# single-gates-SMD.net
KiCad netlist of a schematic drawn in EAGLE
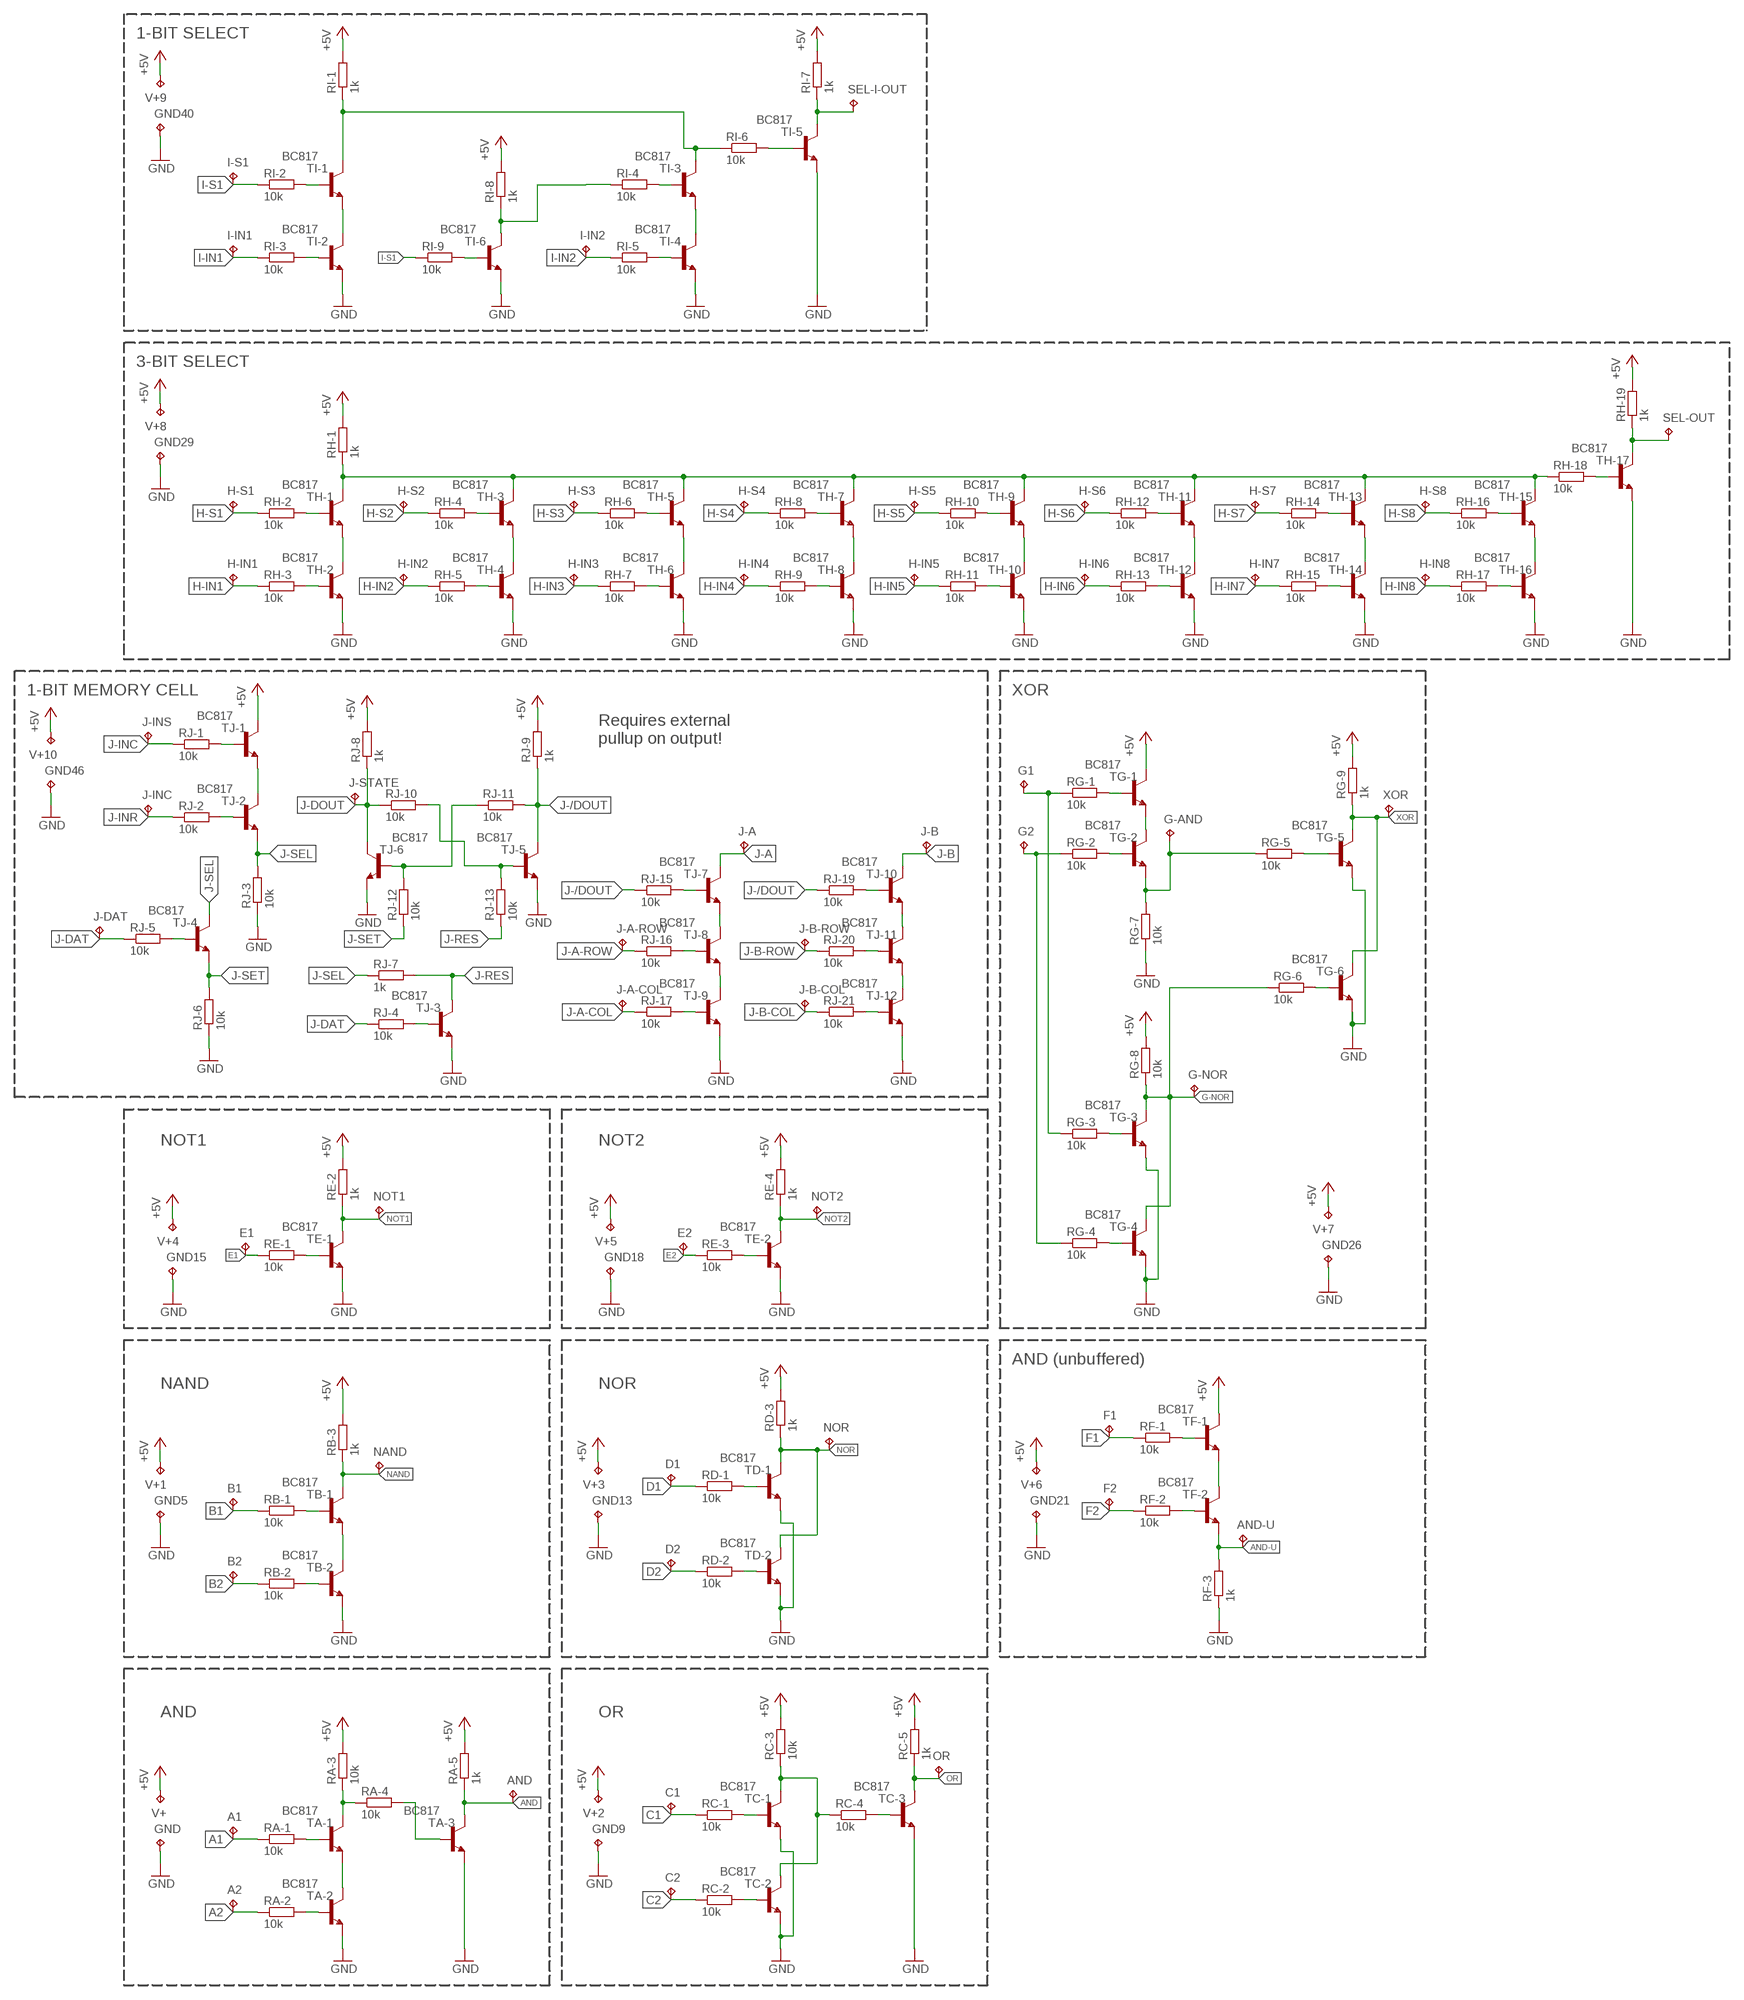
[diagram p0: schematic, sheet 1]

(export (version "E")
  (design (tool "Eeschema 10.0.6"))
  (components
    (comp (ref "A1")
      (value "TPTP07R")
      (footprint "eagle-import:TP07R")
      (libsource (lib "eagle-import") (part "TPTP07R"))
    )
    (comp (ref "A2")
      (value "TPTP07R")
      (footprint "eagle-import:TP07R")
      (libsource (lib "eagle-import") (part "TPTP07R"))
    )
    (comp (ref "AND")
      (value "TPTP07R")
      (footprint "eagle-import:TP07R")
      (libsource (lib "eagle-import") (part "TPTP07R"))
    )
    (comp (ref "AND-U")
      (value "TPTP07R")
      (footprint "eagle-import:TP07R")
      (libsource (lib "eagle-import") (part "TPTP07R"))
    )
    (comp (ref "B1")
      (value "TPTP07R")
      (footprint "eagle-import:TP07R")
      (libsource (lib "eagle-import") (part "TPTP07R"))
    )
    (comp (ref "B2")
      (value "TPTP07R")
      (footprint "eagle-import:TP07R")
      (libsource (lib "eagle-import") (part "TPTP07R"))
    )
    (comp (ref "C1")
      (value "TPTP07R")
      (footprint "eagle-import:TP07R")
      (libsource (lib "eagle-import") (part "TPTP07R"))
    )
    (comp (ref "C2")
      (value "TPTP07R")
      (footprint "eagle-import:TP07R")
      (libsource (lib "eagle-import") (part "TPTP07R"))
    )
    (comp (ref "D1")
      (value "TPTP07R")
      (footprint "eagle-import:TP07R")
      (libsource (lib "eagle-import") (part "TPTP07R"))
    )
    (comp (ref "D2")
      (value "TPTP07R")
      (footprint "eagle-import:TP07R")
      (libsource (lib "eagle-import") (part "TPTP07R"))
    )
    (comp (ref "E1")
      (value "TPTP07R")
      (footprint "eagle-import:TP07R")
      (libsource (lib "eagle-import") (part "TPTP07R"))
    )
    (comp (ref "E2")
      (value "TPTP07R")
      (footprint "eagle-import:TP07R")
      (libsource (lib "eagle-import") (part "TPTP07R"))
    )
    (comp (ref "F1")
      (value "TPTP07R")
      (footprint "eagle-import:TP07R")
      (libsource (lib "eagle-import") (part "TPTP07R"))
    )
    (comp (ref "F2")
      (value "TPTP07R")
      (footprint "eagle-import:TP07R")
      (libsource (lib "eagle-import") (part "TPTP07R"))
    )
    (comp (ref "G-AND")
      (value "TPTP07R")
      (footprint "eagle-import:TP07R")
      (libsource (lib "eagle-import") (part "TPTP07R"))
    )
    (comp (ref "G-NOR")
      (value "TPTP07R")
      (footprint "eagle-import:TP07R")
      (libsource (lib "eagle-import") (part "TPTP07R"))
    )
    (comp (ref "G1")
      (value "TPTP07R")
      (footprint "eagle-import:TP07R")
      (libsource (lib "eagle-import") (part "TPTP07R"))
    )
    (comp (ref "G2")
      (value "TPTP07R")
      (footprint "eagle-import:TP07R")
      (libsource (lib "eagle-import") (part "TPTP07R"))
    )
    (comp (ref "GND")
      (value "TPTP07R")
      (footprint "eagle-import:TP07R")
      (libsource (lib "eagle-import") (part "TPTP07R"))
    )
    (comp (ref "GND5")
      (value "TPTP07R")
      (footprint "eagle-import:TP07R")
      (libsource (lib "eagle-import") (part "TPTP07R"))
    )
    (comp (ref "GND9")
      (value "TPTP07R")
      (footprint "eagle-import:TP07R")
      (libsource (lib "eagle-import") (part "TPTP07R"))
    )
    (comp (ref "GND13")
      (value "TPTP07R")
      (footprint "eagle-import:TP07R")
      (libsource (lib "eagle-import") (part "TPTP07R"))
    )
    (comp (ref "GND15")
      (value "TPTP07R")
      (footprint "eagle-import:TP07R")
      (libsource (lib "eagle-import") (part "TPTP07R"))
    )
    (comp (ref "GND18")
      (value "TPTP07R")
      (footprint "eagle-import:TP07R")
      (libsource (lib "eagle-import") (part "TPTP07R"))
    )
    (comp (ref "GND21")
      (value "TPTP07R")
      (footprint "eagle-import:TP07R")
      (libsource (lib "eagle-import") (part "TPTP07R"))
    )
    (comp (ref "GND26")
      (value "TPTP07R")
      (footprint "eagle-import:TP07R")
      (libsource (lib "eagle-import") (part "TPTP07R"))
    )
    (comp (ref "GND29")
      (value "TPTP07R")
      (footprint "eagle-import:TP07R")
      (libsource (lib "eagle-import") (part "TPTP07R"))
    )
    (comp (ref "GND40")
      (value "TPTP07R")
      (footprint "eagle-import:TP07R")
      (libsource (lib "eagle-import") (part "TPTP07R"))
    )
    (comp (ref "GND46")
      (value "TPTP07R")
      (footprint "eagle-import:TP07R")
      (libsource (lib "eagle-import") (part "TPTP07R"))
    )
    (comp (ref "H-IN1")
      (value "TPTP07R")
      (footprint "eagle-import:TP07R")
      (libsource (lib "eagle-import") (part "TPTP07R"))
    )
    (comp (ref "H-IN2")
      (value "TPTP07R")
      (footprint "eagle-import:TP07R")
      (libsource (lib "eagle-import") (part "TPTP07R"))
    )
    (comp (ref "H-IN3")
      (value "TPTP07R")
      (footprint "eagle-import:TP07R")
      (libsource (lib "eagle-import") (part "TPTP07R"))
    )
    (comp (ref "H-IN4")
      (value "TPTP07R")
      (footprint "eagle-import:TP07R")
      (libsource (lib "eagle-import") (part "TPTP07R"))
    )
    (comp (ref "H-IN5")
      (value "TPTP07R")
      (footprint "eagle-import:TP07R")
      (libsource (lib "eagle-import") (part "TPTP07R"))
    )
    (comp (ref "H-IN6")
      (value "TPTP07R")
      (footprint "eagle-import:TP07R")
      (libsource (lib "eagle-import") (part "TPTP07R"))
    )
    (comp (ref "H-IN7")
      (value "TPTP07R")
      (footprint "eagle-import:TP07R")
      (libsource (lib "eagle-import") (part "TPTP07R"))
    )
    (comp (ref "H-IN8")
      (value "TPTP07R")
      (footprint "eagle-import:TP07R")
      (libsource (lib "eagle-import") (part "TPTP07R"))
    )
    (comp (ref "H-S1")
      (value "TPTP07R")
      (footprint "eagle-import:TP07R")
      (libsource (lib "eagle-import") (part "TPTP07R"))
    )
    (comp (ref "H-S2")
      (value "TPTP07R")
      (footprint "eagle-import:TP07R")
      (libsource (lib "eagle-import") (part "TPTP07R"))
    )
    (comp (ref "H-S3")
      (value "TPTP07R")
      (footprint "eagle-import:TP07R")
      (libsource (lib "eagle-import") (part "TPTP07R"))
    )
    (comp (ref "H-S4")
      (value "TPTP07R")
      (footprint "eagle-import:TP07R")
      (libsource (lib "eagle-import") (part "TPTP07R"))
    )
    (comp (ref "H-S5")
      (value "TPTP07R")
      (footprint "eagle-import:TP07R")
      (libsource (lib "eagle-import") (part "TPTP07R"))
    )
    (comp (ref "H-S6")
      (value "TPTP07R")
      (footprint "eagle-import:TP07R")
      (libsource (lib "eagle-import") (part "TPTP07R"))
    )
    (comp (ref "H-S7")
      (value "TPTP07R")
      (footprint "eagle-import:TP07R")
      (libsource (lib "eagle-import") (part "TPTP07R"))
    )
    (comp (ref "H-S8")
      (value "TPTP07R")
      (footprint "eagle-import:TP07R")
      (libsource (lib "eagle-import") (part "TPTP07R"))
    )
    (comp (ref "I-IN1")
      (value "TPTP07R")
      (footprint "eagle-import:TP07R")
      (libsource (lib "eagle-import") (part "TPTP07R"))
    )
    (comp (ref "I-IN2")
      (value "TPTP07R")
      (footprint "eagle-import:TP07R")
      (libsource (lib "eagle-import") (part "TPTP07R"))
    )
    (comp (ref "I-S1")
      (value "TPTP07R")
      (footprint "eagle-import:TP07R")
      (libsource (lib "eagle-import") (part "TPTP07R"))
    )
    (comp (ref "J-A")
      (value "TPTP07R")
      (footprint "eagle-import:TP07R")
      (libsource (lib "eagle-import") (part "TPTP07R"))
    )
    (comp (ref "J-A-COL")
      (value "TPTP07R")
      (footprint "eagle-import:TP07R")
      (libsource (lib "eagle-import") (part "TPTP07R"))
    )
    (comp (ref "J-A-ROW")
      (value "TPTP07R")
      (footprint "eagle-import:TP07R")
      (libsource (lib "eagle-import") (part "TPTP07R"))
    )
    (comp (ref "J-B")
      (value "TPTP07R")
      (footprint "eagle-import:TP07R")
      (libsource (lib "eagle-import") (part "TPTP07R"))
    )
    (comp (ref "J-B-COL")
      (value "TPTP07R")
      (footprint "eagle-import:TP07R")
      (libsource (lib "eagle-import") (part "TPTP07R"))
    )
    (comp (ref "J-B-ROW")
      (value "TPTP07R")
      (footprint "eagle-import:TP07R")
      (libsource (lib "eagle-import") (part "TPTP07R"))
    )
    (comp (ref "J-DAT")
      (value "TPTP07R")
      (footprint "eagle-import:TP07R")
      (libsource (lib "eagle-import") (part "TPTP07R"))
    )
    (comp (ref "J-INC")
      (value "TPTP07R")
      (footprint "eagle-import:TP07R")
      (libsource (lib "eagle-import") (part "TPTP07R"))
    )
    (comp (ref "J-INS")
      (value "TPTP07R")
      (footprint "eagle-import:TP07R")
      (libsource (lib "eagle-import") (part "TPTP07R"))
    )
    (comp (ref "J-STATE")
      (value "TPTP07R")
      (footprint "eagle-import:TP07R")
      (libsource (lib "eagle-import") (part "TPTP07R"))
    )
    (comp (ref "NAND")
      (value "TPTP07R")
      (footprint "eagle-import:TP07R")
      (libsource (lib "eagle-import") (part "TPTP07R"))
    )
    (comp (ref "NOR")
      (value "TPTP07R")
      (footprint "eagle-import:TP07R")
      (libsource (lib "eagle-import") (part "TPTP07R"))
    )
    (comp (ref "NOT1")
      (value "TPTP07R")
      (footprint "eagle-import:TP07R")
      (libsource (lib "eagle-import") (part "TPTP07R"))
    )
    (comp (ref "NOT2")
      (value "TPTP07R")
      (footprint "eagle-import:TP07R")
      (libsource (lib "eagle-import") (part "TPTP07R"))
    )
    (comp (ref "OR")
      (value "TPTP07R")
      (footprint "eagle-import:TP07R")
      (libsource (lib "eagle-import") (part "TPTP07R"))
    )
    (comp (ref "RA-1")
      (value "10k")
      (footprint "eagle-import:R0603")
      (libsource (lib "eagle-import") (part "R-EU_R0603"))
    )
    (comp (ref "RA-2")
      (value "10k")
      (footprint "eagle-import:R0603")
      (libsource (lib "eagle-import") (part "R-EU_R0603"))
    )
    (comp (ref "RA-3")
      (value "10k")
      (footprint "eagle-import:R0603")
      (libsource (lib "eagle-import") (part "R-EU_R0603"))
    )
    (comp (ref "RA-4")
      (value "10k")
      (footprint "eagle-import:R0603")
      (libsource (lib "eagle-import") (part "R-EU_R0603"))
    )
    (comp (ref "RA-5")
      (value "1k")
      (footprint "eagle-import:R0603")
      (libsource (lib "eagle-import") (part "R-EU_R0603"))
    )
    (comp (ref "RB-1")
      (value "10k")
      (footprint "eagle-import:R0603")
      (libsource (lib "eagle-import") (part "R-EU_R0603"))
    )
    (comp (ref "RB-2")
      (value "10k")
      (footprint "eagle-import:R0603")
      (libsource (lib "eagle-import") (part "R-EU_R0603"))
    )
    (comp (ref "RB-3")
      (value "1k")
      (footprint "eagle-import:R0603")
      (libsource (lib "eagle-import") (part "R-EU_R0603"))
    )
    (comp (ref "RC-1")
      (value "10k")
      (footprint "eagle-import:R0603")
      (libsource (lib "eagle-import") (part "R-EU_R0603"))
    )
    (comp (ref "RC-2")
      (value "10k")
      (footprint "eagle-import:R0603")
      (libsource (lib "eagle-import") (part "R-EU_R0603"))
    )
    (comp (ref "RC-3")
      (value "10k")
      (footprint "eagle-import:R0603")
      (libsource (lib "eagle-import") (part "R-EU_R0603"))
    )
    (comp (ref "RC-4")
      (value "10k")
      (footprint "eagle-import:R0603")
      (libsource (lib "eagle-import") (part "R-EU_R0603"))
    )
    (comp (ref "RC-5")
      (value "1k")
      (footprint "eagle-import:R0603")
      (libsource (lib "eagle-import") (part "R-EU_R0603"))
    )
    (comp (ref "RD-1")
      (value "10k")
      (footprint "eagle-import:R0603")
      (libsource (lib "eagle-import") (part "R-EU_R0603"))
    )
    (comp (ref "RD-2")
      (value "10k")
      (footprint "eagle-import:R0603")
      (libsource (lib "eagle-import") (part "R-EU_R0603"))
    )
    (comp (ref "RD-3")
      (value "1k")
      (footprint "eagle-import:R0603")
      (libsource (lib "eagle-import") (part "R-EU_R0603"))
    )
    (comp (ref "RE-1")
      (value "10k")
      (footprint "eagle-import:R0603")
      (libsource (lib "eagle-import") (part "R-EU_R0603"))
    )
    (comp (ref "RE-2")
      (value "1k")
      (footprint "eagle-import:R0603")
      (libsource (lib "eagle-import") (part "R-EU_R0603"))
    )
    (comp (ref "RE-3")
      (value "10k")
      (footprint "eagle-import:R0603")
      (libsource (lib "eagle-import") (part "R-EU_R0603"))
    )
    (comp (ref "RE-4")
      (value "1k")
      (footprint "eagle-import:R0603")
      (libsource (lib "eagle-import") (part "R-EU_R0603"))
    )
    (comp (ref "RF-1")
      (value "10k")
      (footprint "eagle-import:R0603")
      (libsource (lib "eagle-import") (part "R-EU_R0603"))
    )
    (comp (ref "RF-2")
      (value "10k")
      (footprint "eagle-import:R0603")
      (libsource (lib "eagle-import") (part "R-EU_R0603"))
    )
    (comp (ref "RF-3")
      (value "1k")
      (footprint "eagle-import:R0603")
      (libsource (lib "eagle-import") (part "R-EU_R0603"))
    )
    (comp (ref "RG-1")
      (value "10k")
      (footprint "eagle-import:R0603")
      (libsource (lib "eagle-import") (part "R-EU_R0603"))
    )
    (comp (ref "RG-2")
      (value "10k")
      (footprint "eagle-import:R0603")
      (libsource (lib "eagle-import") (part "R-EU_R0603"))
    )
    (comp (ref "RG-3")
      (value "10k")
      (footprint "eagle-import:R0603")
      (libsource (lib "eagle-import") (part "R-EU_R0603"))
    )
    (comp (ref "RG-4")
      (value "10k")
      (footprint "eagle-import:R0603")
      (libsource (lib "eagle-import") (part "R-EU_R0603"))
    )
    (comp (ref "RG-5")
      (value "10k")
      (footprint "eagle-import:R0603")
      (libsource (lib "eagle-import") (part "R-EU_R0603"))
    )
    (comp (ref "RG-6")
      (value "10k")
      (footprint "eagle-import:R0603")
      (libsource (lib "eagle-import") (part "R-EU_R0603"))
    )
    (comp (ref "RG-7")
      (value "10k")
      (footprint "eagle-import:R0603")
      (libsource (lib "eagle-import") (part "R-EU_R0603"))
    )
    (comp (ref "RG-8")
      (value "10k")
      (footprint "eagle-import:R0603")
      (libsource (lib "eagle-import") (part "R-EU_R0603"))
    )
    (comp (ref "RG-9")
      (value "1k")
      (footprint "eagle-import:R0603")
      (libsource (lib "eagle-import") (part "R-EU_R0603"))
    )
    (comp (ref "RH-1")
      (value "1k")
      (footprint "eagle-import:R0603")
      (libsource (lib "eagle-import") (part "R-EU_R0603"))
    )
    (comp (ref "RH-2")
      (value "10k")
      (footprint "eagle-import:R0603")
      (libsource (lib "eagle-import") (part "R-EU_R0603"))
    )
    (comp (ref "RH-3")
      (value "10k")
      (footprint "eagle-import:R0603")
      (libsource (lib "eagle-import") (part "R-EU_R0603"))
    )
    (comp (ref "RH-4")
      (value "10k")
      (footprint "eagle-import:R0603")
      (libsource (lib "eagle-import") (part "R-EU_R0603"))
    )
    (comp (ref "RH-5")
      (value "10k")
      (footprint "eagle-import:R0603")
      (libsource (lib "eagle-import") (part "R-EU_R0603"))
    )
    (comp (ref "RH-6")
      (value "10k")
      (footprint "eagle-import:R0603")
      (libsource (lib "eagle-import") (part "R-EU_R0603"))
    )
    (comp (ref "RH-7")
      (value "10k")
      (footprint "eagle-import:R0603")
      (libsource (lib "eagle-import") (part "R-EU_R0603"))
    )
    (comp (ref "RH-8")
      (value "10k")
      (footprint "eagle-import:R0603")
      (libsource (lib "eagle-import") (part "R-EU_R0603"))
    )
    (comp (ref "RH-9")
      (value "10k")
      (footprint "eagle-import:R0603")
      (libsource (lib "eagle-import") (part "R-EU_R0603"))
    )
    (comp (ref "RH-10")
      (value "10k")
      (footprint "eagle-import:R0603")
      (libsource (lib "eagle-import") (part "R-EU_R0603"))
    )
    (comp (ref "RH-11")
      (value "10k")
      (footprint "eagle-import:R0603")
      (libsource (lib "eagle-import") (part "R-EU_R0603"))
    )
    (comp (ref "RH-12")
      (value "10k")
      (footprint "eagle-import:R0603")
      (libsource (lib "eagle-import") (part "R-EU_R0603"))
    )
    (comp (ref "RH-13")
      (value "10k")
      (footprint "eagle-import:R0603")
      (libsource (lib "eagle-import") (part "R-EU_R0603"))
    )
    (comp (ref "RH-14")
      (value "10k")
      (footprint "eagle-import:R0603")
      (libsource (lib "eagle-import") (part "R-EU_R0603"))
    )
    (comp (ref "RH-15")
      (value "10k")
      (footprint "eagle-import:R0603")
      (libsource (lib "eagle-import") (part "R-EU_R0603"))
    )
    (comp (ref "RH-16")
      (value "10k")
      (footprint "eagle-import:R0603")
      (libsource (lib "eagle-import") (part "R-EU_R0603"))
    )
    (comp (ref "RH-17")
      (value "10k")
      (footprint "eagle-import:R0603")
      (libsource (lib "eagle-import") (part "R-EU_R0603"))
    )
    (comp (ref "RH-18")
      (value "10k")
      (footprint "eagle-import:R0603")
      (libsource (lib "eagle-import") (part "R-EU_R0603"))
    )
    (comp (ref "RH-19")
      (value "1k")
      (footprint "eagle-import:R0603")
      (libsource (lib "eagle-import") (part "R-EU_R0603"))
    )
    (comp (ref "RI-1")
      (value "1k")
      (footprint "eagle-import:R0603")
      (libsource (lib "eagle-import") (part "R-EU_R0603"))
    )
    (comp (ref "RI-2")
      (value "10k")
      (footprint "eagle-import:R0603")
      (libsource (lib "eagle-import") (part "R-EU_R0603"))
    )
    (comp (ref "RI-3")
      (value "10k")
      (footprint "eagle-import:R0603")
      (libsource (lib "eagle-import") (part "R-EU_R0603"))
    )
    (comp (ref "RI-4")
      (value "10k")
      (footprint "eagle-import:R0603")
      (libsource (lib "eagle-import") (part "R-EU_R0603"))
    )
    (comp (ref "RI-5")
      (value "10k")
      (footprint "eagle-import:R0603")
      (libsource (lib "eagle-import") (part "R-EU_R0603"))
    )
    (comp (ref "RI-6")
      (value "10k")
      (footprint "eagle-import:R0603")
      (libsource (lib "eagle-import") (part "R-EU_R0603"))
    )
    (comp (ref "RI-7")
      (value "1k")
      (footprint "eagle-import:R0603")
      (libsource (lib "eagle-import") (part "R-EU_R0603"))
    )
    (comp (ref "RI-8")
      (value "1k")
      (footprint "eagle-import:R0603")
      (libsource (lib "eagle-import") (part "R-EU_R0603"))
    )
    (comp (ref "RI-9")
      (value "10k")
      (footprint "eagle-import:R0603")
      (libsource (lib "eagle-import") (part "R-EU_R0603"))
    )
    (comp (ref "RJ-1")
      (value "10k")
      (footprint "eagle-import:R0603")
      (libsource (lib "eagle-import") (part "R-EU_R0603"))
    )
    (comp (ref "RJ-2")
      (value "10k")
      (footprint "eagle-import:R0603")
      (libsource (lib "eagle-import") (part "R-EU_R0603"))
    )
    (comp (ref "RJ-3")
      (value "10k")
      (footprint "eagle-import:R0603")
      (libsource (lib "eagle-import") (part "R-EU_R0603"))
    )
    (comp (ref "RJ-4")
      (value "10k")
      (footprint "eagle-import:R0603")
      (libsource (lib "eagle-import") (part "R-EU_R0603"))
    )
    (comp (ref "RJ-5")
      (value "10k")
      (footprint "eagle-import:R0603")
      (libsource (lib "eagle-import") (part "R-EU_R0603"))
    )
    (comp (ref "RJ-6")
      (value "10k")
      (footprint "eagle-import:R0603")
      (libsource (lib "eagle-import") (part "R-EU_R0603"))
    )
    (comp (ref "RJ-7")
      (value "1k")
      (footprint "eagle-import:R0603")
      (libsource (lib "eagle-import") (part "R-EU_R0603"))
    )
    (comp (ref "RJ-8")
      (value "1k")
      (footprint "eagle-import:R0603")
      (libsource (lib "eagle-import") (part "R-EU_R0603"))
    )
    (comp (ref "RJ-9")
      (value "1k")
      (footprint "eagle-import:R0603")
      (libsource (lib "eagle-import") (part "R-EU_R0603"))
    )
    (comp (ref "RJ-10")
      (value "10k")
      (footprint "eagle-import:R0603")
      (libsource (lib "eagle-import") (part "R-EU_R0603"))
    )
    (comp (ref "RJ-11")
      (value "10k")
      (footprint "eagle-import:R0603")
      (libsource (lib "eagle-import") (part "R-EU_R0603"))
    )
    (comp (ref "RJ-12")
      (value "10k")
      (footprint "eagle-import:R0603")
      (libsource (lib "eagle-import") (part "R-EU_R0603"))
    )
    (comp (ref "RJ-13")
      (value "10k")
      (footprint "eagle-import:R0603")
      (libsource (lib "eagle-import") (part "R-EU_R0603"))
    )
    (comp (ref "RJ-15")
      (value "10k")
      (footprint "eagle-import:R0603")
      (libsource (lib "eagle-import") (part "R-EU_R0603"))
    )
    (comp (ref "RJ-16")
      (value "10k")
      (footprint "eagle-import:R0603")
      (libsource (lib "eagle-import") (part "R-EU_R0603"))
    )
    (comp (ref "RJ-17")
      (value "10k")
      (footprint "eagle-import:R0603")
      (libsource (lib "eagle-import") (part "R-EU_R0603"))
    )
    (comp (ref "RJ-19")
      (value "10k")
      (footprint "eagle-import:R0603")
      (libsource (lib "eagle-import") (part "R-EU_R0603"))
    )
    (comp (ref "RJ-20")
      (value "10k")
      (footprint "eagle-import:R0603")
      (libsource (lib "eagle-import") (part "R-EU_R0603"))
    )
    (comp (ref "RJ-21")
      (value "10k")
      (footprint "eagle-import:R0603")
      (libsource (lib "eagle-import") (part "R-EU_R0603"))
    )
    (comp (ref "SEL-I-OUT")
      (value "TPTP07R")
      (footprint "eagle-import:TP07R")
      (libsource (lib "eagle-import") (part "TPTP07R"))
    )
    (comp (ref "SEL-OUT")
      (value "TPTP07R")
      (footprint "eagle-import:TP07R")
      (libsource (lib "eagle-import") (part "TPTP07R"))
    )
    (comp (ref "TA-1")
      (value "BC817")
      (footprint "eagle-import:SOT23-BEC")
      (libsource (lib "eagle-import") (part "-NPN-SOT23-BECBC817-40"))
    )
    (comp (ref "TA-2")
      (value "BC817")
      (footprint "eagle-import:SOT23-BEC")
      (libsource (lib "eagle-import") (part "-NPN-SOT23-BECBC817-40"))
    )
    (comp (ref "TA-3")
      (value "BC817")
      (footprint "eagle-import:SOT23-BEC")
      (libsource (lib "eagle-import") (part "-NPN-SOT23-BECBC817-40"))
    )
    (comp (ref "TB-1")
      (value "BC817")
      (footprint "eagle-import:SOT23-BEC")
      (libsource (lib "eagle-import") (part "-NPN-SOT23-BECBC817-40"))
    )
    (comp (ref "TB-2")
      (value "BC817")
      (footprint "eagle-import:SOT23-BEC")
      (libsource (lib "eagle-import") (part "-NPN-SOT23-BECBC817-40"))
    )
    (comp (ref "TC-1")
      (value "BC817")
      (footprint "eagle-import:SOT23-BEC")
      (libsource (lib "eagle-import") (part "-NPN-SOT23-BECBC817-40"))
    )
    (comp (ref "TC-2")
      (value "BC817")
      (footprint "eagle-import:SOT23-BEC")
      (libsource (lib "eagle-import") (part "-NPN-SOT23-BECBC817-40"))
    )
    (comp (ref "TC-3")
      (value "BC817")
      (footprint "eagle-import:SOT23-BEC")
      (libsource (lib "eagle-import") (part "-NPN-SOT23-BECBC817-40"))
    )
    (comp (ref "TD-1")
      (value "BC817")
      (footprint "eagle-import:SOT23-BEC")
      (libsource (lib "eagle-import") (part "-NPN-SOT23-BECBC817-40"))
    )
    (comp (ref "TD-2")
      (value "BC817")
      (footprint "eagle-import:SOT23-BEC")
      (libsource (lib "eagle-import") (part "-NPN-SOT23-BECBC817-40"))
    )
    (comp (ref "TE-1")
      (value "BC817")
      (footprint "eagle-import:SOT23-BEC")
      (libsource (lib "eagle-import") (part "-NPN-SOT23-BECBC817-40"))
    )
    (comp (ref "TE-2")
      (value "BC817")
      (footprint "eagle-import:SOT23-BEC")
      (libsource (lib "eagle-import") (part "-NPN-SOT23-BECBC817-40"))
    )
    (comp (ref "TF-1")
      (value "BC817")
      (footprint "eagle-import:SOT23-BEC")
      (libsource (lib "eagle-import") (part "-NPN-SOT23-BECBC817-40"))
    )
    (comp (ref "TF-2")
      (value "BC817")
      (footprint "eagle-import:SOT23-BEC")
      (libsource (lib "eagle-import") (part "-NPN-SOT23-BECBC817-40"))
    )
    (comp (ref "TG-1")
      (value "BC817")
      (footprint "eagle-import:SOT23-BEC")
      (libsource (lib "eagle-import") (part "-NPN-SOT23-BECBC817-40"))
    )
    (comp (ref "TG-2")
      (value "BC817")
      (footprint "eagle-import:SOT23-BEC")
      (libsource (lib "eagle-import") (part "-NPN-SOT23-BECBC817-40"))
    )
    (comp (ref "TG-3")
      (value "BC817")
      (footprint "eagle-import:SOT23-BEC")
      (libsource (lib "eagle-import") (part "-NPN-SOT23-BECBC817-40"))
    )
    (comp (ref "TG-4")
      (value "BC817")
      (footprint "eagle-import:SOT23-BEC")
      (libsource (lib "eagle-import") (part "-NPN-SOT23-BECBC817-40"))
    )
    (comp (ref "TG-5")
      (value "BC817")
      (footprint "eagle-import:SOT23-BEC")
      (libsource (lib "eagle-import") (part "-NPN-SOT23-BECBC817-40"))
    )
    (comp (ref "TG-6")
      (value "BC817")
      (footprint "eagle-import:SOT23-BEC")
      (libsource (lib "eagle-import") (part "-NPN-SOT23-BECBC817-40"))
    )
    (comp (ref "TH-1")
      (value "BC817")
      (footprint "eagle-import:SOT23-BEC")
      (libsource (lib "eagle-import") (part "-NPN-SOT23-BECBC817-40"))
    )
    (comp (ref "TH-2")
      (value "BC817")
      (footprint "eagle-import:SOT23-BEC")
      (libsource (lib "eagle-import") (part "-NPN-SOT23-BECBC817-40"))
    )
    (comp (ref "TH-3")
      (value "BC817")
      (footprint "eagle-import:SOT23-BEC")
      (libsource (lib "eagle-import") (part "-NPN-SOT23-BECBC817-40"))
    )
    (comp (ref "TH-4")
      (value "BC817")
      (footprint "eagle-import:SOT23-BEC")
      (libsource (lib "eagle-import") (part "-NPN-SOT23-BECBC817-40"))
    )
    (comp (ref "TH-5")
      (value "BC817")
      (footprint "eagle-import:SOT23-BEC")
      (libsource (lib "eagle-import") (part "-NPN-SOT23-BECBC817-40"))
    )
    (comp (ref "TH-6")
      (value "BC817")
      (footprint "eagle-import:SOT23-BEC")
      (libsource (lib "eagle-import") (part "-NPN-SOT23-BECBC817-40"))
    )
    (comp (ref "TH-7")
      (value "BC817")
      (footprint "eagle-import:SOT23-BEC")
      (libsource (lib "eagle-import") (part "-NPN-SOT23-BECBC817-40"))
    )
    (comp (ref "TH-8")
      (value "BC817")
      (footprint "eagle-import:SOT23-BEC")
      (libsource (lib "eagle-import") (part "-NPN-SOT23-BECBC817-40"))
    )
    (comp (ref "TH-9")
      (value "BC817")
      (footprint "eagle-import:SOT23-BEC")
      (libsource (lib "eagle-import") (part "-NPN-SOT23-BECBC817-40"))
    )
    (comp (ref "TH-10")
      (value "BC817")
      (footprint "eagle-import:SOT23-BEC")
      (libsource (lib "eagle-import") (part "-NPN-SOT23-BECBC817-40"))
    )
    (comp (ref "TH-11")
      (value "BC817")
      (footprint "eagle-import:SOT23-BEC")
      (libsource (lib "eagle-import") (part "-NPN-SOT23-BECBC817-40"))
    )
    (comp (ref "TH-12")
      (value "BC817")
      (footprint "eagle-import:SOT23-BEC")
      (libsource (lib "eagle-import") (part "-NPN-SOT23-BECBC817-40"))
    )
    (comp (ref "TH-13")
      (value "BC817")
      (footprint "eagle-import:SOT23-BEC")
      (libsource (lib "eagle-import") (part "-NPN-SOT23-BECBC817-40"))
    )
    (comp (ref "TH-14")
      (value "BC817")
      (footprint "eagle-import:SOT23-BEC")
      (libsource (lib "eagle-import") (part "-NPN-SOT23-BECBC817-40"))
    )
    (comp (ref "TH-15")
      (value "BC817")
      (footprint "eagle-import:SOT23-BEC")
      (libsource (lib "eagle-import") (part "-NPN-SOT23-BECBC817-40"))
    )
    (comp (ref "TH-16")
      (value "BC817")
      (footprint "eagle-import:SOT23-BEC")
      (libsource (lib "eagle-import") (part "-NPN-SOT23-BECBC817-40"))
    )
    (comp (ref "TH-17")
      (value "BC817")
      (footprint "eagle-import:SOT23-BEC")
      (libsource (lib "eagle-import") (part "-NPN-SOT23-BECBC817-40"))
    )
    (comp (ref "TI-1")
      (value "BC817")
      (footprint "eagle-import:SOT23-BEC")
      (libsource (lib "eagle-import") (part "-NPN-SOT23-BECBC817-40"))
    )
    (comp (ref "TI-2")
      (value "BC817")
      (footprint "eagle-import:SOT23-BEC")
      (libsource (lib "eagle-import") (part "-NPN-SOT23-BECBC817-40"))
    )
    (comp (ref "TI-3")
      (value "BC817")
      (footprint "eagle-import:SOT23-BEC")
      (libsource (lib "eagle-import") (part "-NPN-SOT23-BECBC817-40"))
    )
    (comp (ref "TI-4")
      (value "BC817")
      (footprint "eagle-import:SOT23-BEC")
      (libsource (lib "eagle-import") (part "-NPN-SOT23-BECBC817-40"))
    )
    (comp (ref "TI-5")
      (value "BC817")
      (footprint "eagle-import:SOT23-BEC")
      (libsource (lib "eagle-import") (part "-NPN-SOT23-BECBC817-40"))
    )
    (comp (ref "TI-6")
      (value "BC817")
      (footprint "eagle-import:SOT23-BEC")
      (libsource (lib "eagle-import") (part "-NPN-SOT23-BECBC817-40"))
    )
    (comp (ref "TJ-1")
      (value "BC817")
      (footprint "eagle-import:SOT23-BEC")
      (libsource (lib "eagle-import") (part "-NPN-SOT23-BECBC817-40"))
    )
    (comp (ref "TJ-2")
      (value "BC817")
      (footprint "eagle-import:SOT23-BEC")
      (libsource (lib "eagle-import") (part "-NPN-SOT23-BECBC817-40"))
    )
    (comp (ref "TJ-3")
      (value "BC817")
      (footprint "eagle-import:SOT23-BEC")
      (libsource (lib "eagle-import") (part "-NPN-SOT23-BECBC817-40"))
    )
    (comp (ref "TJ-4")
      (value "BC817")
      (footprint "eagle-import:SOT23-BEC")
      (libsource (lib "eagle-import") (part "-NPN-SOT23-BECBC817-40"))
    )
    (comp (ref "TJ-5")
      (value "BC817")
      (footprint "eagle-import:SOT23-BEC")
      (libsource (lib "eagle-import") (part "-NPN-SOT23-BECBC817-40"))
    )
    (comp (ref "TJ-6")
      (value "BC817")
      (footprint "eagle-import:SOT23-BEC")
      (libsource (lib "eagle-import") (part "-NPN-SOT23-BECBC817-40"))
    )
    (comp (ref "TJ-7")
      (value "BC817")
      (footprint "eagle-import:SOT23-BEC")
      (libsource (lib "eagle-import") (part "-NPN-SOT23-BECBC817-40"))
    )
    (comp (ref "TJ-8")
      (value "BC817")
      (footprint "eagle-import:SOT23-BEC")
      (libsource (lib "eagle-import") (part "-NPN-SOT23-BECBC817-40"))
    )
    (comp (ref "TJ-9")
      (value "BC817")
      (footprint "eagle-import:SOT23-BEC")
      (libsource (lib "eagle-import") (part "-NPN-SOT23-BECBC817-40"))
    )
    (comp (ref "TJ-10")
      (value "BC817")
      (footprint "eagle-import:SOT23-BEC")
      (libsource (lib "eagle-import") (part "-NPN-SOT23-BECBC817-40"))
    )
    (comp (ref "TJ-11")
      (value "BC817")
      (footprint "eagle-import:SOT23-BEC")
      (libsource (lib "eagle-import") (part "-NPN-SOT23-BECBC817-40"))
    )
    (comp (ref "TJ-12")
      (value "BC817")
      (footprint "eagle-import:SOT23-BEC")
      (libsource (lib "eagle-import") (part "-NPN-SOT23-BECBC817-40"))
    )
    (comp (ref "V+")
      (value "TPTP07R")
      (footprint "eagle-import:TP07R")
      (libsource (lib "eagle-import") (part "TPTP07R"))
    )
    (comp (ref "V+1")
      (value "TPTP07R")
      (footprint "eagle-import:TP07R")
      (libsource (lib "eagle-import") (part "TPTP07R"))
    )
    (comp (ref "V+2")
      (value "TPTP07R")
      (footprint "eagle-import:TP07R")
      (libsource (lib "eagle-import") (part "TPTP07R"))
    )
    (comp (ref "V+3")
      (value "TPTP07R")
      (footprint "eagle-import:TP07R")
      (libsource (lib "eagle-import") (part "TPTP07R"))
    )
    (comp (ref "V+4")
      (value "TPTP07R")
      (footprint "eagle-import:TP07R")
      (libsource (lib "eagle-import") (part "TPTP07R"))
    )
    (comp (ref "V+5")
      (value "TPTP07R")
      (footprint "eagle-import:TP07R")
      (libsource (lib "eagle-import") (part "TPTP07R"))
    )
    (comp (ref "V+6")
      (value "TPTP07R")
      (footprint "eagle-import:TP07R")
      (libsource (lib "eagle-import") (part "TPTP07R"))
    )
    (comp (ref "V+7")
      (value "TPTP07R")
      (footprint "eagle-import:TP07R")
      (libsource (lib "eagle-import") (part "TPTP07R"))
    )
    (comp (ref "V+8")
      (value "TPTP07R")
      (footprint "eagle-import:TP07R")
      (libsource (lib "eagle-import") (part "TPTP07R"))
    )
    (comp (ref "V+9")
      (value "TPTP07R")
      (footprint "eagle-import:TP07R")
      (libsource (lib "eagle-import") (part "TPTP07R"))
    )
    (comp (ref "V+10")
      (value "TPTP07R")
      (footprint "eagle-import:TP07R")
      (libsource (lib "eagle-import") (part "TPTP07R"))
    )
    (comp (ref "XOR")
      (value "TPTP07R")
      (footprint "eagle-import:TP07R")
      (libsource (lib "eagle-import") (part "TPTP07R"))
    )
  )
  (nets
    (net (code "1") (name "+5V") (class "Default")
      (node (ref "RA-3") (pin "2") (pinfunction "2_2") (pintype "passive"))
      (node (ref "RA-5") (pin "2") (pinfunction "2_2") (pintype "passive"))
      (node (ref "RB-3") (pin "2") (pinfunction "2_2") (pintype "passive"))
      (node (ref "RC-3") (pin "2") (pinfunction "2_2") (pintype "passive"))
      (node (ref "RC-5") (pin "2") (pinfunction "2_2") (pintype "passive"))
      (node (ref "RD-3") (pin "2") (pinfunction "2_2") (pintype "passive"))
      (node (ref "RE-2") (pin "2") (pinfunction "2_2") (pintype "passive"))
      (node (ref "RE-4") (pin "2") (pinfunction "2_2") (pintype "passive"))
      (node (ref "RG-8") (pin "2") (pinfunction "2_2") (pintype "passive"))
      (node (ref "RG-9") (pin "2") (pinfunction "2_2") (pintype "passive"))
      (node (ref "RH-1") (pin "2") (pinfunction "2_2") (pintype "passive"))
      (node (ref "RH-19") (pin "2") (pinfunction "2_2") (pintype "passive"))
      (node (ref "RI-1") (pin "2") (pinfunction "2_2") (pintype "passive"))
      (node (ref "RI-7") (pin "2") (pinfunction "2_2") (pintype "passive"))
      (node (ref "RI-8") (pin "2") (pinfunction "2_2") (pintype "passive"))
      (node (ref "RJ-8") (pin "2") (pinfunction "2_2") (pintype "passive"))
      (node (ref "RJ-9") (pin "2") (pinfunction "2_2") (pintype "passive"))
      (node (ref "TF-1") (pin "C") (pinfunction "C_C") (pintype "passive"))
      (node (ref "TG-1") (pin "C") (pinfunction "C_C") (pintype "passive"))
      (node (ref "TJ-1") (pin "C") (pinfunction "C_C") (pintype "passive"))
      (node (ref "V+") (pin "TP") (pinfunction "TP_TP") (pintype "input"))
      (node (ref "V+1") (pin "TP") (pinfunction "TP_TP") (pintype "input"))
      (node (ref "V+10") (pin "TP") (pinfunction "TP_TP") (pintype "input"))
      (node (ref "V+2") (pin "TP") (pinfunction "TP_TP") (pintype "input"))
      (node (ref "V+3") (pin "TP") (pinfunction "TP_TP") (pintype "input"))
      (node (ref "V+4") (pin "TP") (pinfunction "TP_TP") (pintype "input"))
      (node (ref "V+5") (pin "TP") (pinfunction "TP_TP") (pintype "input"))
      (node (ref "V+6") (pin "TP") (pinfunction "TP_TP") (pintype "input"))
      (node (ref "V+7") (pin "TP") (pinfunction "TP_TP") (pintype "input"))
      (node (ref "V+8") (pin "TP") (pinfunction "TP_TP") (pintype "input"))
      (node (ref "V+9") (pin "TP") (pinfunction "TP_TP") (pintype "input"))
    )
    (net (code "2") (name "A1") (class "Default")
      (node (ref "A1") (pin "TP") (pinfunction "TP_TP") (pintype "input"))
      (node (ref "RA-1") (pin "1") (pinfunction "1_1") (pintype "passive"))
    )
    (net (code "3") (name "A2") (class "Default")
      (node (ref "A2") (pin "TP") (pinfunction "TP_TP") (pintype "input"))
      (node (ref "RA-2") (pin "1") (pinfunction "1_1") (pintype "passive"))
    )
    (net (code "4") (name "AND") (class "Default")
      (node (ref "AND") (pin "TP") (pinfunction "TP_TP") (pintype "input"))
      (node (ref "RA-5") (pin "1") (pinfunction "1_1") (pintype "passive"))
      (node (ref "TA-3") (pin "C") (pinfunction "C_C") (pintype "passive"))
    )
    (net (code "5") (name "AND-U") (class "Default")
      (node (ref "AND-U") (pin "TP") (pinfunction "TP_TP") (pintype "input"))
      (node (ref "RF-3") (pin "2") (pinfunction "2_2") (pintype "passive"))
      (node (ref "TF-2") (pin "E") (pinfunction "E_E") (pintype "passive"))
    )
    (net (code "6") (name "B1") (class "Default")
      (node (ref "B1") (pin "TP") (pinfunction "TP_TP") (pintype "input"))
      (node (ref "RB-1") (pin "1") (pinfunction "1_1") (pintype "passive"))
    )
    (net (code "7") (name "B2") (class "Default")
      (node (ref "B2") (pin "TP") (pinfunction "TP_TP") (pintype "input"))
      (node (ref "RB-2") (pin "1") (pinfunction "1_1") (pintype "passive"))
    )
    (net (code "8") (name "C1") (class "Default")
      (node (ref "C1") (pin "TP") (pinfunction "TP_TP") (pintype "input"))
      (node (ref "RC-1") (pin "1") (pinfunction "1_1") (pintype "passive"))
    )
    (net (code "9") (name "C2") (class "Default")
      (node (ref "C2") (pin "TP") (pinfunction "TP_TP") (pintype "input"))
      (node (ref "RC-2") (pin "1") (pinfunction "1_1") (pintype "passive"))
    )
    (net (code "10") (name "D1") (class "Default")
      (node (ref "D1") (pin "TP") (pinfunction "TP_TP") (pintype "input"))
      (node (ref "RD-1") (pin "1") (pinfunction "1_1") (pintype "passive"))
    )
    (net (code "11") (name "D2") (class "Default")
      (node (ref "D2") (pin "TP") (pinfunction "TP_TP") (pintype "input"))
      (node (ref "RD-2") (pin "1") (pinfunction "1_1") (pintype "passive"))
    )
    (net (code "12") (name "E1") (class "Default")
      (node (ref "E1") (pin "TP") (pinfunction "TP_TP") (pintype "input"))
      (node (ref "RE-1") (pin "1") (pinfunction "1_1") (pintype "passive"))
    )
    (net (code "13") (name "E2") (class "Default")
      (node (ref "E2") (pin "TP") (pinfunction "TP_TP") (pintype "input"))
      (node (ref "RE-3") (pin "1") (pinfunction "1_1") (pintype "passive"))
    )
    (net (code "14") (name "F1") (class "Default")
      (node (ref "F1") (pin "TP") (pinfunction "TP_TP") (pintype "input"))
      (node (ref "RF-1") (pin "1") (pinfunction "1_1") (pintype "passive"))
    )
    (net (code "15") (name "F2") (class "Default")
      (node (ref "F2") (pin "TP") (pinfunction "TP_TP") (pintype "input"))
      (node (ref "RF-2") (pin "1") (pinfunction "1_1") (pintype "passive"))
    )
    (net (code "16") (name "G-NOR") (class "Default")
      (node (ref "G-NOR") (pin "TP") (pinfunction "TP_TP") (pintype "input"))
      (node (ref "RG-6") (pin "1") (pinfunction "1_1") (pintype "passive"))
      (node (ref "RG-8") (pin "1") (pinfunction "1_1") (pintype "passive"))
      (node (ref "TG-3") (pin "C") (pinfunction "C_C") (pintype "passive"))
      (node (ref "TG-4") (pin "C") (pinfunction "C_C") (pintype "passive"))
    )
    (net (code "17") (name "GND") (class "Default")
      (node (ref "GND") (pin "TP") (pinfunction "TP_TP") (pintype "input"))
      (node (ref "GND13") (pin "TP") (pinfunction "TP_TP") (pintype "input"))
      (node (ref "GND15") (pin "TP") (pinfunction "TP_TP") (pintype "input"))
      (node (ref "GND18") (pin "TP") (pinfunction "TP_TP") (pintype "input"))
      (node (ref "GND21") (pin "TP") (pinfunction "TP_TP") (pintype "input"))
      (node (ref "GND26") (pin "TP") (pinfunction "TP_TP") (pintype "input"))
      (node (ref "GND29") (pin "TP") (pinfunction "TP_TP") (pintype "input"))
      (node (ref "GND40") (pin "TP") (pinfunction "TP_TP") (pintype "input"))
      (node (ref "GND46") (pin "TP") (pinfunction "TP_TP") (pintype "input"))
      (node (ref "GND5") (pin "TP") (pinfunction "TP_TP") (pintype "input"))
      (node (ref "GND9") (pin "TP") (pinfunction "TP_TP") (pintype "input"))
      (node (ref "RF-3") (pin "1") (pinfunction "1_1") (pintype "passive"))
      (node (ref "RG-7") (pin "1") (pinfunction "1_1") (pintype "passive"))
      (node (ref "RJ-3") (pin "1") (pinfunction "1_1") (pintype "passive"))
      (node (ref "RJ-6") (pin "1") (pinfunction "1_1") (pintype "passive"))
      (node (ref "TA-2") (pin "E") (pinfunction "E_E") (pintype "passive"))
      (node (ref "TA-3") (pin "E") (pinfunction "E_E") (pintype "passive"))
      (node (ref "TB-2") (pin "E") (pinfunction "E_E") (pintype "passive"))
      (node (ref "TC-1") (pin "E") (pinfunction "E_E") (pintype "passive"))
      (node (ref "TC-2") (pin "E") (pinfunction "E_E") (pintype "passive"))
      (node (ref "TC-3") (pin "E") (pinfunction "E_E") (pintype "passive"))
      (node (ref "TD-1") (pin "E") (pinfunction "E_E") (pintype "passive"))
      (node (ref "TD-2") (pin "E") (pinfunction "E_E") (pintype "passive"))
      (node (ref "TE-1") (pin "E") (pinfunction "E_E") (pintype "passive"))
      (node (ref "TE-2") (pin "E") (pinfunction "E_E") (pintype "passive"))
      (node (ref "TG-3") (pin "E") (pinfunction "E_E") (pintype "passive"))
      (node (ref "TG-4") (pin "E") (pinfunction "E_E") (pintype "passive"))
      (node (ref "TG-5") (pin "E") (pinfunction "E_E") (pintype "passive"))
      (node (ref "TG-6") (pin "E") (pinfunction "E_E") (pintype "passive"))
      (node (ref "TH-10") (pin "E") (pinfunction "E_E") (pintype "passive"))
      (node (ref "TH-12") (pin "E") (pinfunction "E_E") (pintype "passive"))
      (node (ref "TH-14") (pin "E") (pinfunction "E_E") (pintype "passive"))
      (node (ref "TH-16") (pin "E") (pinfunction "E_E") (pintype "passive"))
      (node (ref "TH-17") (pin "E") (pinfunction "E_E") (pintype "passive"))
      (node (ref "TH-2") (pin "E") (pinfunction "E_E") (pintype "passive"))
      (node (ref "TH-4") (pin "E") (pinfunction "E_E") (pintype "passive"))
      (node (ref "TH-6") (pin "E") (pinfunction "E_E") (pintype "passive"))
      (node (ref "TH-8") (pin "E") (pinfunction "E_E") (pintype "passive"))
      (node (ref "TI-2") (pin "E") (pinfunction "E_E") (pintype "passive"))
      (node (ref "TI-4") (pin "E") (pinfunction "E_E") (pintype "passive"))
      (node (ref "TI-5") (pin "E") (pinfunction "E_E") (pintype "passive"))
      (node (ref "TI-6") (pin "E") (pinfunction "E_E") (pintype "passive"))
      (node (ref "TJ-12") (pin "E") (pinfunction "E_E") (pintype "passive"))
      (node (ref "TJ-3") (pin "E") (pinfunction "E_E") (pintype "passive"))
      (node (ref "TJ-5") (pin "E") (pinfunction "E_E") (pintype "passive"))
      (node (ref "TJ-6") (pin "E") (pinfunction "E_E") (pintype "passive"))
      (node (ref "TJ-9") (pin "E") (pinfunction "E_E") (pintype "passive"))
    )
    (net (code "18") (name "H-IN1") (class "Default")
      (node (ref "H-IN1") (pin "TP") (pinfunction "TP_TP") (pintype "input"))
      (node (ref "RH-3") (pin "1") (pinfunction "1_1") (pintype "passive"))
    )
    (net (code "19") (name "H-IN2") (class "Default")
      (node (ref "H-IN2") (pin "TP") (pinfunction "TP_TP") (pintype "input"))
      (node (ref "RH-5") (pin "1") (pinfunction "1_1") (pintype "passive"))
    )
    (net (code "20") (name "H-IN3") (class "Default")
      (node (ref "H-IN3") (pin "TP") (pinfunction "TP_TP") (pintype "input"))
      (node (ref "RH-7") (pin "1") (pinfunction "1_1") (pintype "passive"))
    )
    (net (code "21") (name "H-IN4") (class "Default")
      (node (ref "H-IN4") (pin "TP") (pinfunction "TP_TP") (pintype "input"))
      (node (ref "RH-9") (pin "1") (pinfunction "1_1") (pintype "passive"))
    )
    (net (code "22") (name "H-IN5") (class "Default")
      (node (ref "H-IN5") (pin "TP") (pinfunction "TP_TP") (pintype "input"))
      (node (ref "RH-11") (pin "1") (pinfunction "1_1") (pintype "passive"))
    )
    (net (code "23") (name "H-IN6") (class "Default")
      (node (ref "H-IN6") (pin "TP") (pinfunction "TP_TP") (pintype "input"))
      (node (ref "RH-13") (pin "1") (pinfunction "1_1") (pintype "passive"))
    )
    (net (code "24") (name "H-IN7") (class "Default")
      (node (ref "H-IN7") (pin "TP") (pinfunction "TP_TP") (pintype "input"))
      (node (ref "RH-15") (pin "1") (pinfunction "1_1") (pintype "passive"))
    )
    (net (code "25") (name "H-IN8") (class "Default")
      (node (ref "H-IN8") (pin "TP") (pinfunction "TP_TP") (pintype "input"))
      (node (ref "RH-17") (pin "1") (pinfunction "1_1") (pintype "passive"))
    )
    (net (code "26") (name "H-S1") (class "Default")
      (node (ref "H-S1") (pin "TP") (pinfunction "TP_TP") (pintype "input"))
      (node (ref "RH-2") (pin "1") (pinfunction "1_1") (pintype "passive"))
    )
    (net (code "27") (name "H-S2") (class "Default")
      (node (ref "H-S2") (pin "TP") (pinfunction "TP_TP") (pintype "input"))
      (node (ref "RH-4") (pin "1") (pinfunction "1_1") (pintype "passive"))
    )
    (net (code "28") (name "H-S3") (class "Default")
      (node (ref "H-S3") (pin "TP") (pinfunction "TP_TP") (pintype "input"))
      (node (ref "RH-6") (pin "1") (pinfunction "1_1") (pintype "passive"))
    )
    (net (code "29") (name "H-S4") (class "Default")
      (node (ref "H-S4") (pin "TP") (pinfunction "TP_TP") (pintype "input"))
      (node (ref "RH-8") (pin "1") (pinfunction "1_1") (pintype "passive"))
    )
    (net (code "30") (name "H-S5") (class "Default")
      (node (ref "H-S5") (pin "TP") (pinfunction "TP_TP") (pintype "input"))
      (node (ref "RH-10") (pin "1") (pinfunction "1_1") (pintype "passive"))
    )
    (net (code "31") (name "H-S6") (class "Default")
      (node (ref "H-S6") (pin "TP") (pinfunction "TP_TP") (pintype "input"))
      (node (ref "RH-12") (pin "1") (pinfunction "1_1") (pintype "passive"))
    )
    (net (code "32") (name "H-S7") (class "Default")
      (node (ref "H-S7") (pin "TP") (pinfunction "TP_TP") (pintype "input"))
      (node (ref "RH-14") (pin "1") (pinfunction "1_1") (pintype "passive"))
    )
    (net (code "33") (name "H-S8") (class "Default")
      (node (ref "H-S8") (pin "TP") (pinfunction "TP_TP") (pintype "input"))
      (node (ref "RH-16") (pin "1") (pinfunction "1_1") (pintype "passive"))
    )
    (net (code "34") (name "I-IN1") (class "Default")
      (node (ref "I-IN1") (pin "TP") (pinfunction "TP_TP") (pintype "input"))
      (node (ref "RI-3") (pin "1") (pinfunction "1_1") (pintype "passive"))
    )
    (net (code "35") (name "I-IN2") (class "Default")
      (node (ref "I-IN2") (pin "TP") (pinfunction "TP_TP") (pintype "input"))
      (node (ref "RI-5") (pin "1") (pinfunction "1_1") (pintype "passive"))
    )
    (net (code "36") (name "I-S1") (class "Default")
      (node (ref "I-S1") (pin "TP") (pinfunction "TP_TP") (pintype "input"))
      (node (ref "RI-2") (pin "1") (pinfunction "1_1") (pintype "passive"))
      (node (ref "RI-9") (pin "1") (pinfunction "1_1") (pintype "passive"))
    )
    (net (code "37") (name "J-A") (class "Default")
      (node (ref "J-A") (pin "TP") (pinfunction "TP_TP") (pintype "input"))
      (node (ref "TJ-7") (pin "C") (pinfunction "C_C") (pintype "passive"))
    )
    (net (code "38") (name "J-A-COL") (class "Default")
      (node (ref "J-A-COL") (pin "TP") (pinfunction "TP_TP") (pintype "input"))
      (node (ref "RJ-17") (pin "1") (pinfunction "1_1") (pintype "passive"))
    )
    (net (code "39") (name "J-A-ROW") (class "Default")
      (node (ref "J-A-ROW") (pin "TP") (pinfunction "TP_TP") (pintype "input"))
      (node (ref "RJ-16") (pin "1") (pinfunction "1_1") (pintype "passive"))
    )
    (net (code "40") (name "J-B") (class "Default")
      (node (ref "J-B") (pin "TP") (pinfunction "TP_TP") (pintype "input"))
      (node (ref "TJ-10") (pin "C") (pinfunction "C_C") (pintype "passive"))
    )
    (net (code "41") (name "J-B-COL") (class "Default")
      (node (ref "J-B-COL") (pin "TP") (pinfunction "TP_TP") (pintype "input"))
      (node (ref "RJ-21") (pin "1") (pinfunction "1_1") (pintype "passive"))
    )
    (net (code "42") (name "J-B-ROW") (class "Default")
      (node (ref "J-B-ROW") (pin "TP") (pinfunction "TP_TP") (pintype "input"))
      (node (ref "RJ-20") (pin "1") (pinfunction "1_1") (pintype "passive"))
    )
    (net (code "43") (name "J-DAT") (class "Default")
      (node (ref "J-DAT") (pin "TP") (pinfunction "TP_TP") (pintype "input"))
      (node (ref "RJ-4") (pin "1") (pinfunction "1_1") (pintype "passive"))
      (node (ref "RJ-5") (pin "1") (pinfunction "1_1") (pintype "passive"))
    )
    (net (code "44") (name "J-DOUT") (class "Default")
      (node (ref "J-STATE") (pin "TP") (pinfunction "TP_TP") (pintype "input"))
      (node (ref "RJ-10") (pin "1") (pinfunction "1_1") (pintype "passive"))
      (node (ref "RJ-8") (pin "1") (pinfunction "1_1") (pintype "passive"))
      (node (ref "TJ-6") (pin "C") (pinfunction "C_C") (pintype "passive"))
    )
    (net (code "45") (name "J-INC") (class "Default")
      (node (ref "J-INS") (pin "TP") (pinfunction "TP_TP") (pintype "input"))
      (node (ref "RJ-1") (pin "1") (pinfunction "1_1") (pintype "passive"))
    )
    (net (code "46") (name "J-INR") (class "Default")
      (node (ref "J-INC") (pin "TP") (pinfunction "TP_TP") (pintype "input"))
      (node (ref "RJ-2") (pin "1") (pinfunction "1_1") (pintype "passive"))
    )
    (net (code "47") (name "J-RES") (class "Default")
      (node (ref "RJ-13") (pin "1") (pinfunction "1_1") (pintype "passive"))
      (node (ref "RJ-7") (pin "2") (pinfunction "2_2") (pintype "passive"))
      (node (ref "TJ-3") (pin "C") (pinfunction "C_C") (pintype "passive"))
    )
    (net (code "48") (name "J-SEL") (class "Default")
      (node (ref "RJ-3") (pin "2") (pinfunction "2_2") (pintype "passive"))
      (node (ref "RJ-7") (pin "1") (pinfunction "1_1") (pintype "passive"))
      (node (ref "TJ-2") (pin "E") (pinfunction "E_E") (pintype "passive"))
      (node (ref "TJ-4") (pin "C") (pinfunction "C_C") (pintype "passive"))
    )
    (net (code "49") (name "J-SET") (class "Default")
      (node (ref "RJ-12") (pin "1") (pinfunction "1_1") (pintype "passive"))
      (node (ref "RJ-6") (pin "2") (pinfunction "2_2") (pintype "passive"))
      (node (ref "TJ-4") (pin "E") (pinfunction "E_E") (pintype "passive"))
    )
    (net (code "50") (name "J-{slash}DOUT") (class "Default")
      (node (ref "RJ-11") (pin "2") (pinfunction "2_2") (pintype "passive"))
      (node (ref "RJ-15") (pin "1") (pinfunction "1_1") (pintype "passive"))
      (node (ref "RJ-19") (pin "1") (pinfunction "1_1") (pintype "passive"))
      (node (ref "RJ-9") (pin "1") (pinfunction "1_1") (pintype "passive"))
      (node (ref "TJ-5") (pin "C") (pinfunction "C_C") (pintype "passive"))
    )
    (net (code "51") (name "NAND") (class "Default")
      (node (ref "NAND") (pin "TP") (pinfunction "TP_TP") (pintype "input"))
      (node (ref "RB-3") (pin "1") (pinfunction "1_1") (pintype "passive"))
      (node (ref "TB-1") (pin "C") (pinfunction "C_C") (pintype "passive"))
    )
    (net (code "52") (name "NOR") (class "Default")
      (node (ref "NOR") (pin "TP") (pinfunction "TP_TP") (pintype "input"))
      (node (ref "RD-3") (pin "1") (pinfunction "1_1") (pintype "passive"))
      (node (ref "TD-1") (pin "C") (pinfunction "C_C") (pintype "passive"))
      (node (ref "TD-2") (pin "C") (pinfunction "C_C") (pintype "passive"))
    )
    (net (code "53") (name "NOT1") (class "Default")
      (node (ref "NOT1") (pin "TP") (pinfunction "TP_TP") (pintype "input"))
      (node (ref "RE-2") (pin "1") (pinfunction "1_1") (pintype "passive"))
      (node (ref "TE-1") (pin "C") (pinfunction "C_C") (pintype "passive"))
    )
    (net (code "54") (name "NOT2") (class "Default")
      (node (ref "NOT2") (pin "TP") (pinfunction "TP_TP") (pintype "input"))
      (node (ref "RE-4") (pin "1") (pinfunction "1_1") (pintype "passive"))
      (node (ref "TE-2") (pin "C") (pinfunction "C_C") (pintype "passive"))
    )
    (net (code "55") (name "Net-(G-AND-PadTP)") (class "Default")
      (node (ref "G-AND") (pin "TP") (pinfunction "TP_TP") (pintype "input"))
      (node (ref "RG-5") (pin "1") (pinfunction "1_1") (pintype "passive"))
      (node (ref "RG-7") (pin "2") (pinfunction "2_2") (pintype "passive"))
      (node (ref "TG-2") (pin "E") (pinfunction "E_E") (pintype "passive"))
    )
    (net (code "56") (name "Net-(G1-PadTP)") (class "Default")
      (node (ref "G1") (pin "TP") (pinfunction "TP_TP") (pintype "input"))
      (node (ref "RG-1") (pin "1") (pinfunction "1_1") (pintype "passive"))
      (node (ref "RG-3") (pin "1") (pinfunction "1_1") (pintype "passive"))
    )
    (net (code "57") (name "Net-(G2-PadTP)") (class "Default")
      (node (ref "G2") (pin "TP") (pinfunction "TP_TP") (pintype "input"))
      (node (ref "RG-2") (pin "1") (pinfunction "1_1") (pintype "passive"))
      (node (ref "RG-4") (pin "1") (pinfunction "1_1") (pintype "passive"))
    )
    (net (code "58") (name "Net-(RA-1-Pad2)") (class "Default")
      (node (ref "RA-1") (pin "2") (pinfunction "2_2") (pintype "passive"))
      (node (ref "TA-1") (pin "B") (pinfunction "B_B") (pintype "passive"))
    )
    (net (code "59") (name "Net-(RA-2-Pad2)") (class "Default")
      (node (ref "RA-2") (pin "2") (pinfunction "2_2") (pintype "passive"))
      (node (ref "TA-2") (pin "B") (pinfunction "B_B") (pintype "passive"))
    )
    (net (code "60") (name "Net-(RA-3-Pad1)") (class "Default")
      (node (ref "RA-3") (pin "1") (pinfunction "1_1") (pintype "passive"))
      (node (ref "RA-4") (pin "1") (pinfunction "1_1") (pintype "passive"))
      (node (ref "TA-1") (pin "C") (pinfunction "C_C") (pintype "passive"))
    )
    (net (code "61") (name "Net-(RA-4-Pad2)") (class "Default")
      (node (ref "RA-4") (pin "2") (pinfunction "2_2") (pintype "passive"))
      (node (ref "TA-3") (pin "B") (pinfunction "B_B") (pintype "passive"))
    )
    (net (code "62") (name "Net-(RB-1-Pad2)") (class "Default")
      (node (ref "RB-1") (pin "2") (pinfunction "2_2") (pintype "passive"))
      (node (ref "TB-1") (pin "B") (pinfunction "B_B") (pintype "passive"))
    )
    (net (code "63") (name "Net-(RB-2-Pad2)") (class "Default")
      (node (ref "RB-2") (pin "2") (pinfunction "2_2") (pintype "passive"))
      (node (ref "TB-2") (pin "B") (pinfunction "B_B") (pintype "passive"))
    )
    (net (code "64") (name "Net-(RC-1-Pad2)") (class "Default")
      (node (ref "RC-1") (pin "2") (pinfunction "2_2") (pintype "passive"))
      (node (ref "TC-1") (pin "B") (pinfunction "B_B") (pintype "passive"))
    )
    (net (code "65") (name "Net-(RC-2-Pad2)") (class "Default")
      (node (ref "RC-2") (pin "2") (pinfunction "2_2") (pintype "passive"))
      (node (ref "TC-2") (pin "B") (pinfunction "B_B") (pintype "passive"))
    )
    (net (code "66") (name "Net-(RC-3-Pad1)") (class "Default")
      (node (ref "RC-3") (pin "1") (pinfunction "1_1") (pintype "passive"))
      (node (ref "RC-4") (pin "1") (pinfunction "1_1") (pintype "passive"))
      (node (ref "TC-1") (pin "C") (pinfunction "C_C") (pintype "passive"))
      (node (ref "TC-2") (pin "C") (pinfunction "C_C") (pintype "passive"))
    )
    (net (code "67") (name "Net-(RC-4-Pad2)") (class "Default")
      (node (ref "RC-4") (pin "2") (pinfunction "2_2") (pintype "passive"))
      (node (ref "TC-3") (pin "B") (pinfunction "B_B") (pintype "passive"))
    )
    (net (code "68") (name "Net-(RD-1-Pad2)") (class "Default")
      (node (ref "RD-1") (pin "2") (pinfunction "2_2") (pintype "passive"))
      (node (ref "TD-1") (pin "B") (pinfunction "B_B") (pintype "passive"))
    )
    (net (code "69") (name "Net-(RD-2-Pad2)") (class "Default")
      (node (ref "RD-2") (pin "2") (pinfunction "2_2") (pintype "passive"))
      (node (ref "TD-2") (pin "B") (pinfunction "B_B") (pintype "passive"))
    )
    (net (code "70") (name "Net-(RE-1-Pad2)") (class "Default")
      (node (ref "RE-1") (pin "2") (pinfunction "2_2") (pintype "passive"))
      (node (ref "TE-1") (pin "B") (pinfunction "B_B") (pintype "passive"))
    )
    (net (code "71") (name "Net-(RE-3-Pad2)") (class "Default")
      (node (ref "RE-3") (pin "2") (pinfunction "2_2") (pintype "passive"))
      (node (ref "TE-2") (pin "B") (pinfunction "B_B") (pintype "passive"))
    )
    (net (code "72") (name "Net-(RF-1-Pad2)") (class "Default")
      (node (ref "RF-1") (pin "2") (pinfunction "2_2") (pintype "passive"))
      (node (ref "TF-1") (pin "B") (pinfunction "B_B") (pintype "passive"))
    )
    (net (code "73") (name "Net-(RF-2-Pad2)") (class "Default")
      (node (ref "RF-2") (pin "2") (pinfunction "2_2") (pintype "passive"))
      (node (ref "TF-2") (pin "B") (pinfunction "B_B") (pintype "passive"))
    )
    (net (code "74") (name "Net-(RG-1-Pad2)") (class "Default")
      (node (ref "RG-1") (pin "2") (pinfunction "2_2") (pintype "passive"))
      (node (ref "TG-1") (pin "B") (pinfunction "B_B") (pintype "passive"))
    )
    (net (code "75") (name "Net-(RG-2-Pad2)") (class "Default")
      (node (ref "RG-2") (pin "2") (pinfunction "2_2") (pintype "passive"))
      (node (ref "TG-2") (pin "B") (pinfunction "B_B") (pintype "passive"))
    )
    (net (code "76") (name "Net-(RG-3-Pad2)") (class "Default")
      (node (ref "RG-3") (pin "2") (pinfunction "2_2") (pintype "passive"))
      (node (ref "TG-3") (pin "B") (pinfunction "B_B") (pintype "passive"))
    )
    (net (code "77") (name "Net-(RG-4-Pad2)") (class "Default")
      (node (ref "RG-4") (pin "2") (pinfunction "2_2") (pintype "passive"))
      (node (ref "TG-4") (pin "B") (pinfunction "B_B") (pintype "passive"))
    )
    (net (code "78") (name "Net-(RG-5-Pad2)") (class "Default")
      (node (ref "RG-5") (pin "2") (pinfunction "2_2") (pintype "passive"))
      (node (ref "TG-5") (pin "B") (pinfunction "B_B") (pintype "passive"))
    )
    (net (code "79") (name "Net-(RG-6-Pad2)") (class "Default")
      (node (ref "RG-6") (pin "2") (pinfunction "2_2") (pintype "passive"))
      (node (ref "TG-6") (pin "B") (pinfunction "B_B") (pintype "passive"))
    )
    (net (code "80") (name "Net-(RH-1-Pad1)") (class "Default")
      (node (ref "RH-1") (pin "1") (pinfunction "1_1") (pintype "passive"))
      (node (ref "RH-18") (pin "1") (pinfunction "1_1") (pintype "passive"))
      (node (ref "TH-1") (pin "C") (pinfunction "C_C") (pintype "passive"))
      (node (ref "TH-11") (pin "C") (pinfunction "C_C") (pintype "passive"))
      (node (ref "TH-13") (pin "C") (pinfunction "C_C") (pintype "passive"))
      (node (ref "TH-15") (pin "C") (pinfunction "C_C") (pintype "passive"))
      (node (ref "TH-3") (pin "C") (pinfunction "C_C") (pintype "passive"))
      (node (ref "TH-5") (pin "C") (pinfunction "C_C") (pintype "passive"))
      (node (ref "TH-7") (pin "C") (pinfunction "C_C") (pintype "passive"))
      (node (ref "TH-9") (pin "C") (pinfunction "C_C") (pintype "passive"))
    )
    (net (code "81") (name "Net-(RH-2-Pad2)") (class "Default")
      (node (ref "RH-2") (pin "2") (pinfunction "2_2") (pintype "passive"))
      (node (ref "TH-1") (pin "B") (pinfunction "B_B") (pintype "passive"))
    )
    (net (code "82") (name "Net-(RH-3-Pad2)") (class "Default")
      (node (ref "RH-3") (pin "2") (pinfunction "2_2") (pintype "passive"))
      (node (ref "TH-2") (pin "B") (pinfunction "B_B") (pintype "passive"))
    )
    (net (code "83") (name "Net-(RH-4-Pad2)") (class "Default")
      (node (ref "RH-4") (pin "2") (pinfunction "2_2") (pintype "passive"))
      (node (ref "TH-3") (pin "B") (pinfunction "B_B") (pintype "passive"))
    )
    (net (code "84") (name "Net-(RH-5-Pad2)") (class "Default")
      (node (ref "RH-5") (pin "2") (pinfunction "2_2") (pintype "passive"))
      (node (ref "TH-4") (pin "B") (pinfunction "B_B") (pintype "passive"))
    )
    (net (code "85") (name "Net-(RH-6-Pad2)") (class "Default")
      (node (ref "RH-6") (pin "2") (pinfunction "2_2") (pintype "passive"))
      (node (ref "TH-5") (pin "B") (pinfunction "B_B") (pintype "passive"))
    )
    (net (code "86") (name "Net-(RH-7-Pad2)") (class "Default")
      (node (ref "RH-7") (pin "2") (pinfunction "2_2") (pintype "passive"))
      (node (ref "TH-6") (pin "B") (pinfunction "B_B") (pintype "passive"))
    )
    (net (code "87") (name "Net-(RH-8-Pad2)") (class "Default")
      (node (ref "RH-8") (pin "2") (pinfunction "2_2") (pintype "passive"))
      (node (ref "TH-7") (pin "B") (pinfunction "B_B") (pintype "passive"))
    )
    (net (code "88") (name "Net-(RH-9-Pad2)") (class "Default")
      (node (ref "RH-9") (pin "2") (pinfunction "2_2") (pintype "passive"))
      (node (ref "TH-8") (pin "B") (pinfunction "B_B") (pintype "passive"))
    )
    (net (code "89") (name "Net-(RH-10-Pad2)") (class "Default")
      (node (ref "RH-10") (pin "2") (pinfunction "2_2") (pintype "passive"))
      (node (ref "TH-9") (pin "B") (pinfunction "B_B") (pintype "passive"))
    )
    (net (code "90") (name "Net-(RH-11-Pad2)") (class "Default")
      (node (ref "RH-11") (pin "2") (pinfunction "2_2") (pintype "passive"))
      (node (ref "TH-10") (pin "B") (pinfunction "B_B") (pintype "passive"))
    )
    (net (code "91") (name "Net-(RH-12-Pad2)") (class "Default")
      (node (ref "RH-12") (pin "2") (pinfunction "2_2") (pintype "passive"))
      (node (ref "TH-11") (pin "B") (pinfunction "B_B") (pintype "passive"))
    )
    (net (code "92") (name "Net-(RH-13-Pad2)") (class "Default")
      (node (ref "RH-13") (pin "2") (pinfunction "2_2") (pintype "passive"))
      (node (ref "TH-12") (pin "B") (pinfunction "B_B") (pintype "passive"))
    )
    (net (code "93") (name "Net-(RH-14-Pad2)") (class "Default")
      (node (ref "RH-14") (pin "2") (pinfunction "2_2") (pintype "passive"))
      (node (ref "TH-13") (pin "B") (pinfunction "B_B") (pintype "passive"))
    )
    (net (code "94") (name "Net-(RH-15-Pad2)") (class "Default")
      (node (ref "RH-15") (pin "2") (pinfunction "2_2") (pintype "passive"))
      (node (ref "TH-14") (pin "B") (pinfunction "B_B") (pintype "passive"))
    )
    (net (code "95") (name "Net-(RH-16-Pad2)") (class "Default")
      (node (ref "RH-16") (pin "2") (pinfunction "2_2") (pintype "passive"))
      (node (ref "TH-15") (pin "B") (pinfunction "B_B") (pintype "passive"))
    )
    (net (code "96") (name "Net-(RH-17-Pad2)") (class "Default")
      (node (ref "RH-17") (pin "2") (pinfunction "2_2") (pintype "passive"))
      (node (ref "TH-16") (pin "B") (pinfunction "B_B") (pintype "passive"))
    )
    (net (code "97") (name "Net-(RH-18-Pad2)") (class "Default")
      (node (ref "RH-18") (pin "2") (pinfunction "2_2") (pintype "passive"))
      (node (ref "TH-17") (pin "B") (pinfunction "B_B") (pintype "passive"))
    )
    (net (code "98") (name "Net-(RH-19-Pad1)") (class "Default")
      (node (ref "RH-19") (pin "1") (pinfunction "1_1") (pintype "passive"))
      (node (ref "SEL-OUT") (pin "TP") (pinfunction "TP_TP") (pintype "input"))
      (node (ref "TH-17") (pin "C") (pinfunction "C_C") (pintype "passive"))
    )
    (net (code "99") (name "Net-(RI-1-Pad1)") (class "Default")
      (node (ref "RI-1") (pin "1") (pinfunction "1_1") (pintype "passive"))
      (node (ref "RI-6") (pin "1") (pinfunction "1_1") (pintype "passive"))
      (node (ref "TI-1") (pin "C") (pinfunction "C_C") (pintype "passive"))
      (node (ref "TI-3") (pin "C") (pinfunction "C_C") (pintype "passive"))
    )
    (net (code "100") (name "Net-(RI-2-Pad2)") (class "Default")
      (node (ref "RI-2") (pin "2") (pinfunction "2_2") (pintype "passive"))
      (node (ref "TI-1") (pin "B") (pinfunction "B_B") (pintype "passive"))
    )
    (net (code "101") (name "Net-(RI-3-Pad2)") (class "Default")
      (node (ref "RI-3") (pin "2") (pinfunction "2_2") (pintype "passive"))
      (node (ref "TI-2") (pin "B") (pinfunction "B_B") (pintype "passive"))
    )
    (net (code "102") (name "Net-(RI-4-Pad1)") (class "Default")
      (node (ref "RI-4") (pin "1") (pinfunction "1_1") (pintype "passive"))
      (node (ref "RI-8") (pin "1") (pinfunction "1_1") (pintype "passive"))
      (node (ref "TI-6") (pin "C") (pinfunction "C_C") (pintype "passive"))
    )
    (net (code "103") (name "Net-(RI-4-Pad2)") (class "Default")
      (node (ref "RI-4") (pin "2") (pinfunction "2_2") (pintype "passive"))
      (node (ref "TI-3") (pin "B") (pinfunction "B_B") (pintype "passive"))
    )
    (net (code "104") (name "Net-(RI-5-Pad2)") (class "Default")
      (node (ref "RI-5") (pin "2") (pinfunction "2_2") (pintype "passive"))
      (node (ref "TI-4") (pin "B") (pinfunction "B_B") (pintype "passive"))
    )
    (net (code "105") (name "Net-(RI-6-Pad2)") (class "Default")
      (node (ref "RI-6") (pin "2") (pinfunction "2_2") (pintype "passive"))
      (node (ref "TI-5") (pin "B") (pinfunction "B_B") (pintype "passive"))
    )
    (net (code "106") (name "Net-(RI-7-Pad1)") (class "Default")
      (node (ref "RI-7") (pin "1") (pinfunction "1_1") (pintype "passive"))
      (node (ref "SEL-I-OUT") (pin "TP") (pinfunction "TP_TP") (pintype "input"))
      (node (ref "TI-5") (pin "C") (pinfunction "C_C") (pintype "passive"))
    )
    (net (code "107") (name "Net-(RI-9-Pad2)") (class "Default")
      (node (ref "RI-9") (pin "2") (pinfunction "2_2") (pintype "passive"))
      (node (ref "TI-6") (pin "B") (pinfunction "B_B") (pintype "passive"))
    )
    (net (code "108") (name "Net-(RJ-1-Pad2)") (class "Default")
      (node (ref "RJ-1") (pin "2") (pinfunction "2_2") (pintype "passive"))
      (node (ref "TJ-1") (pin "B") (pinfunction "B_B") (pintype "passive"))
    )
    (net (code "109") (name "Net-(RJ-2-Pad2)") (class "Default")
      (node (ref "RJ-2") (pin "2") (pinfunction "2_2") (pintype "passive"))
      (node (ref "TJ-2") (pin "B") (pinfunction "B_B") (pintype "passive"))
    )
    (net (code "110") (name "Net-(RJ-4-Pad2)") (class "Default")
      (node (ref "RJ-4") (pin "2") (pinfunction "2_2") (pintype "passive"))
      (node (ref "TJ-3") (pin "B") (pinfunction "B_B") (pintype "passive"))
    )
    (net (code "111") (name "Net-(RJ-5-Pad2)") (class "Default")
      (node (ref "RJ-5") (pin "2") (pinfunction "2_2") (pintype "passive"))
      (node (ref "TJ-4") (pin "B") (pinfunction "B_B") (pintype "passive"))
    )
    (net (code "112") (name "Net-(RJ-10-Pad2)") (class "Default")
      (node (ref "RJ-10") (pin "2") (pinfunction "2_2") (pintype "passive"))
      (node (ref "RJ-13") (pin "2") (pinfunction "2_2") (pintype "passive"))
      (node (ref "TJ-5") (pin "B") (pinfunction "B_B") (pintype "passive"))
    )
    (net (code "113") (name "Net-(RJ-11-Pad1)") (class "Default")
      (node (ref "RJ-11") (pin "1") (pinfunction "1_1") (pintype "passive"))
      (node (ref "RJ-12") (pin "2") (pinfunction "2_2") (pintype "passive"))
      (node (ref "TJ-6") (pin "B") (pinfunction "B_B") (pintype "passive"))
    )
    (net (code "114") (name "Net-(RJ-15-Pad2)") (class "Default")
      (node (ref "RJ-15") (pin "2") (pinfunction "2_2") (pintype "passive"))
      (node (ref "TJ-7") (pin "B") (pinfunction "B_B") (pintype "passive"))
    )
    (net (code "115") (name "Net-(RJ-16-Pad2)") (class "Default")
      (node (ref "RJ-16") (pin "2") (pinfunction "2_2") (pintype "passive"))
      (node (ref "TJ-8") (pin "B") (pinfunction "B_B") (pintype "passive"))
    )
    (net (code "116") (name "Net-(RJ-17-Pad2)") (class "Default")
      (node (ref "RJ-17") (pin "2") (pinfunction "2_2") (pintype "passive"))
      (node (ref "TJ-9") (pin "B") (pinfunction "B_B") (pintype "passive"))
    )
    (net (code "117") (name "Net-(RJ-19-Pad2)") (class "Default")
      (node (ref "RJ-19") (pin "2") (pinfunction "2_2") (pintype "passive"))
      (node (ref "TJ-10") (pin "B") (pinfunction "B_B") (pintype "passive"))
    )
    (net (code "118") (name "Net-(RJ-20-Pad2)") (class "Default")
      (node (ref "RJ-20") (pin "2") (pinfunction "2_2") (pintype "passive"))
      (node (ref "TJ-11") (pin "B") (pinfunction "B_B") (pintype "passive"))
    )
    (net (code "119") (name "Net-(RJ-21-Pad2)") (class "Default")
      (node (ref "RJ-21") (pin "2") (pinfunction "2_2") (pintype "passive"))
      (node (ref "TJ-12") (pin "B") (pinfunction "B_B") (pintype "passive"))
    )
    (net (code "120") (name "Net-(TA-1-PadE)") (class "Default")
      (node (ref "TA-1") (pin "E") (pinfunction "E_E") (pintype "passive"))
      (node (ref "TA-2") (pin "C") (pinfunction "C_C") (pintype "passive"))
    )
    (net (code "121") (name "Net-(TB-1-PadE)") (class "Default")
      (node (ref "TB-1") (pin "E") (pinfunction "E_E") (pintype "passive"))
      (node (ref "TB-2") (pin "C") (pinfunction "C_C") (pintype "passive"))
    )
    (net (code "122") (name "Net-(TF-1-PadE)") (class "Default")
      (node (ref "TF-1") (pin "E") (pinfunction "E_E") (pintype "passive"))
      (node (ref "TF-2") (pin "C") (pinfunction "C_C") (pintype "passive"))
    )
    (net (code "123") (name "Net-(TG-1-PadE)") (class "Default")
      (node (ref "TG-1") (pin "E") (pinfunction "E_E") (pintype "passive"))
      (node (ref "TG-2") (pin "C") (pinfunction "C_C") (pintype "passive"))
    )
    (net (code "124") (name "Net-(TH-1-PadE)") (class "Default")
      (node (ref "TH-1") (pin "E") (pinfunction "E_E") (pintype "passive"))
      (node (ref "TH-2") (pin "C") (pinfunction "C_C") (pintype "passive"))
    )
    (net (code "125") (name "Net-(TH-3-PadE)") (class "Default")
      (node (ref "TH-3") (pin "E") (pinfunction "E_E") (pintype "passive"))
      (node (ref "TH-4") (pin "C") (pinfunction "C_C") (pintype "passive"))
    )
    (net (code "126") (name "Net-(TH-5-PadE)") (class "Default")
      (node (ref "TH-5") (pin "E") (pinfunction "E_E") (pintype "passive"))
      (node (ref "TH-6") (pin "C") (pinfunction "C_C") (pintype "passive"))
    )
    (net (code "127") (name "Net-(TH-7-PadE)") (class "Default")
      (node (ref "TH-7") (pin "E") (pinfunction "E_E") (pintype "passive"))
      (node (ref "TH-8") (pin "C") (pinfunction "C_C") (pintype "passive"))
    )
    (net (code "128") (name "Net-(TH-10-PadC)") (class "Default")
      (node (ref "TH-10") (pin "C") (pinfunction "C_C") (pintype "passive"))
      (node (ref "TH-9") (pin "E") (pinfunction "E_E") (pintype "passive"))
    )
    (net (code "129") (name "Net-(TH-11-PadE)") (class "Default")
      (node (ref "TH-11") (pin "E") (pinfunction "E_E") (pintype "passive"))
      (node (ref "TH-12") (pin "C") (pinfunction "C_C") (pintype "passive"))
    )
    (net (code "130") (name "Net-(TH-13-PadE)") (class "Default")
      (node (ref "TH-13") (pin "E") (pinfunction "E_E") (pintype "passive"))
      (node (ref "TH-14") (pin "C") (pinfunction "C_C") (pintype "passive"))
    )
    (net (code "131") (name "Net-(TH-15-PadE)") (class "Default")
      (node (ref "TH-15") (pin "E") (pinfunction "E_E") (pintype "passive"))
      (node (ref "TH-16") (pin "C") (pinfunction "C_C") (pintype "passive"))
    )
    (net (code "132") (name "Net-(TI-1-PadE)") (class "Default")
      (node (ref "TI-1") (pin "E") (pinfunction "E_E") (pintype "passive"))
      (node (ref "TI-2") (pin "C") (pinfunction "C_C") (pintype "passive"))
    )
    (net (code "133") (name "Net-(TI-3-PadE)") (class "Default")
      (node (ref "TI-3") (pin "E") (pinfunction "E_E") (pintype "passive"))
      (node (ref "TI-4") (pin "C") (pinfunction "C_C") (pintype "passive"))
    )
    (net (code "134") (name "Net-(TJ-1-PadE)") (class "Default")
      (node (ref "TJ-1") (pin "E") (pinfunction "E_E") (pintype "passive"))
      (node (ref "TJ-2") (pin "C") (pinfunction "C_C") (pintype "passive"))
    )
    (net (code "135") (name "Net-(TJ-7-PadE)") (class "Default")
      (node (ref "TJ-7") (pin "E") (pinfunction "E_E") (pintype "passive"))
      (node (ref "TJ-8") (pin "C") (pinfunction "C_C") (pintype "passive"))
    )
    (net (code "136") (name "Net-(TJ-8-PadE)") (class "Default")
      (node (ref "TJ-8") (pin "E") (pinfunction "E_E") (pintype "passive"))
      (node (ref "TJ-9") (pin "C") (pinfunction "C_C") (pintype "passive"))
    )
    (net (code "137") (name "Net-(TJ-10-PadE)") (class "Default")
      (node (ref "TJ-10") (pin "E") (pinfunction "E_E") (pintype "passive"))
      (node (ref "TJ-11") (pin "C") (pinfunction "C_C") (pintype "passive"))
    )
    (net (code "138") (name "Net-(TJ-11-PadE)") (class "Default")
      (node (ref "TJ-11") (pin "E") (pinfunction "E_E") (pintype "passive"))
      (node (ref "TJ-12") (pin "C") (pinfunction "C_C") (pintype "passive"))
    )
    (net (code "139") (name "OR") (class "Default")
      (node (ref "OR") (pin "TP") (pinfunction "TP_TP") (pintype "input"))
      (node (ref "RC-5") (pin "1") (pinfunction "1_1") (pintype "passive"))
      (node (ref "TC-3") (pin "C") (pinfunction "C_C") (pintype "passive"))
    )
    (net (code "140") (name "XOR") (class "Default")
      (node (ref "RG-9") (pin "1") (pinfunction "1_1") (pintype "passive"))
      (node (ref "TG-5") (pin "C") (pinfunction "C_C") (pintype "passive"))
      (node (ref "TG-6") (pin "C") (pinfunction "C_C") (pintype "passive"))
      (node (ref "XOR") (pin "TP") (pinfunction "TP_TP") (pintype "input"))
    )
  )
)
